# Triple_Phase_Bridge.net
KiCad netlist of a schematic drawn in Altium Designer
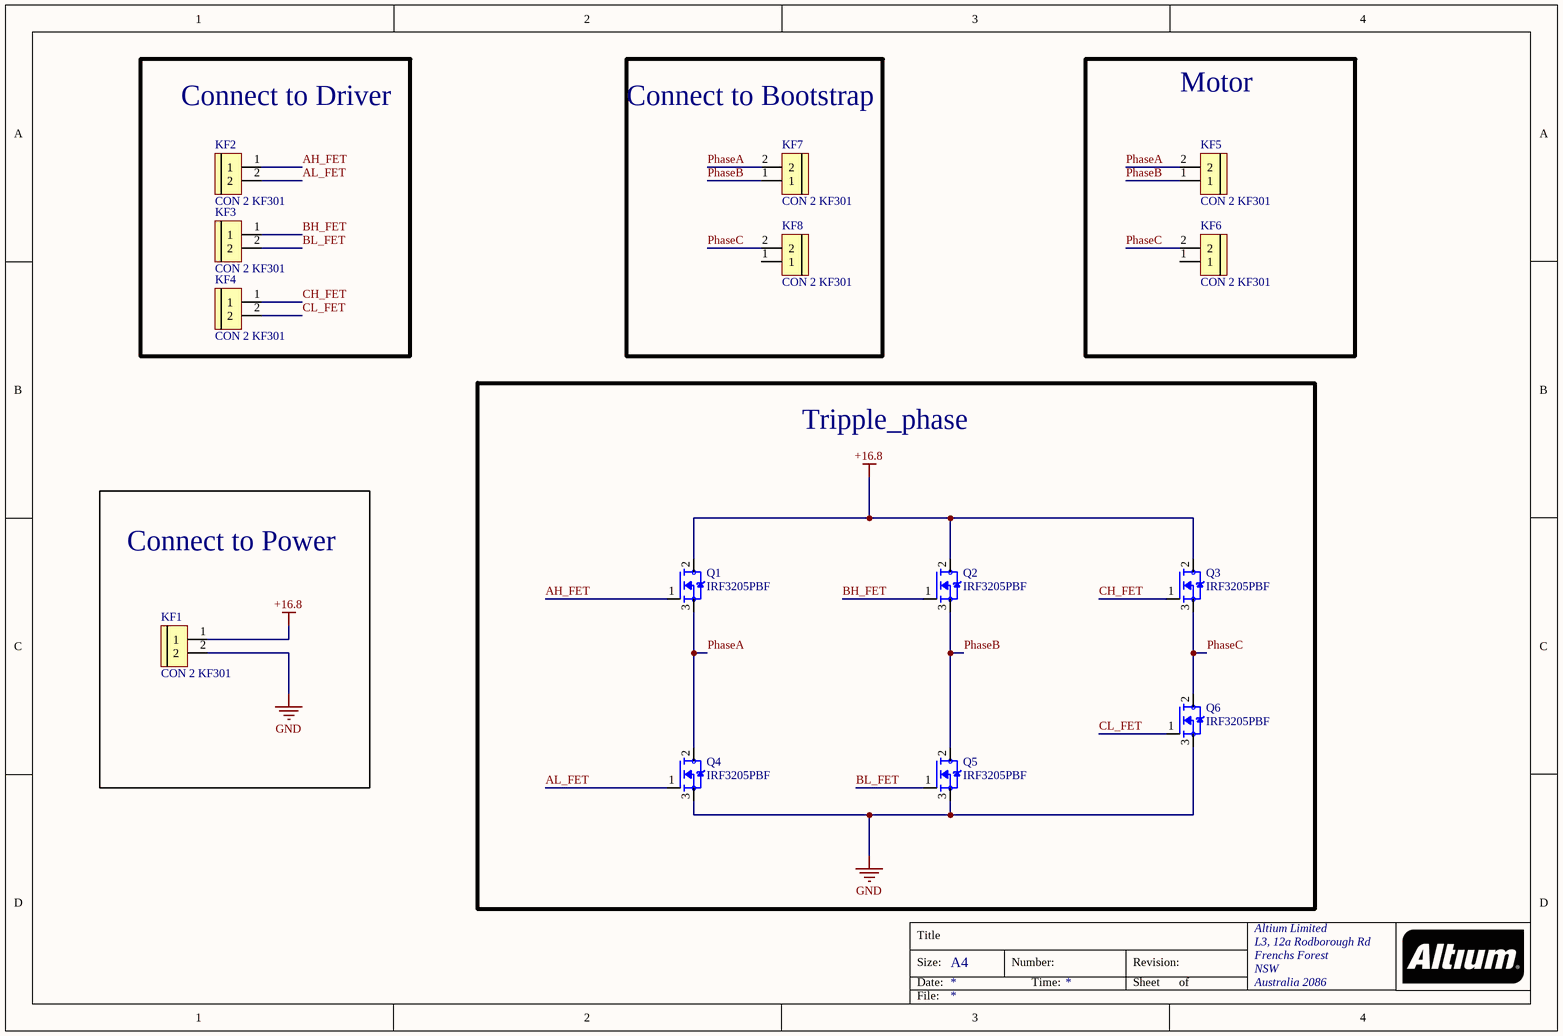
[diagram p0: Triple_Phase_Bridge.SchDoc]

(export (version "E")
  (design (tool "Eeschema 10.0.6"))
  (components
    (comp (ref "KF1")
      (value "CON 2 KF301")
      (footprint "Con 2 KF301 5.08")
      (description "Cắm")
      (libsource (lib "Connector") (part "CON 2 KF301"))
    )
    (comp (ref "KF2")
      (value "CON 2 KF301")
      (footprint "Con 2 KF301 5.08")
      (description "Cắm")
      (libsource (lib "Connector") (part "CON 2 KF301"))
    )
    (comp (ref "KF3")
      (value "CON 2 KF301")
      (footprint "Con 2 KF301 5.08")
      (description "Cắm")
      (libsource (lib "Connector") (part "CON 2 KF301"))
    )
    (comp (ref "KF4")
      (value "CON 2 KF301")
      (footprint "Con 2 KF301 5.08")
      (description "Cắm")
      (libsource (lib "Connector") (part "CON 2 KF301"))
    )
    (comp (ref "KF5")
      (value "CON 2 KF301")
      (footprint "Con 2 KF301 5.08")
      (description "Cắm")
      (libsource (lib "") (part "CON 2 KF301_1"))
    )
    (comp (ref "KF6")
      (value "CON 2 KF301")
      (footprint "Con 2 KF301 5.08")
      (description "Cắm")
      (libsource (lib "") (part "CON 2 KF301_1"))
    )
    (comp (ref "KF7")
      (value "CON 2 KF301")
      (footprint "Con 2 KF301 5.08")
      (description "Cắm")
      (libsource (lib "") (part "CON 2 KF301_1"))
    )
    (comp (ref "KF8")
      (value "CON 2 KF301")
      (footprint "Con 2 KF301 5.08")
      (description "Cắm")
      (libsource (lib "") (part "CON 2 KF301_1"))
    )
    (comp (ref "Q1")
      (value "IRF3205PBF")
      (footprint "TO254P1067X483X3124-3P")
      (description "N-Channel 55V 110A _Tc_ 200W _Tc_ Through Hole TO-220AB")
      (fields (field (name "MF") "Infineon Technologies"))
      (libsource (lib "IRF3205PBF") (part "IRF3205PBF"))
    )
    (comp (ref "Q2")
      (value "IRF3205PBF")
      (footprint "TO254P1067X483X3124-3P")
      (description "N-Channel 55V 110A _Tc_ 200W _Tc_ Through Hole TO-220AB")
      (fields (field (name "MF") "Infineon Technologies"))
      (libsource (lib "IRF3205PBF") (part "IRF3205PBF"))
    )
    (comp (ref "Q3")
      (value "IRF3205PBF")
      (footprint "TO254P1067X483X3124-3P")
      (description "N-Channel 55V 110A _Tc_ 200W _Tc_ Through Hole TO-220AB")
      (fields (field (name "MF") "Infineon Technologies"))
      (libsource (lib "IRF3205PBF") (part "IRF3205PBF"))
    )
    (comp (ref "Q4")
      (value "IRF3205PBF")
      (footprint "TO254P1067X483X3124-3P")
      (description "N-Channel 55V 110A _Tc_ 200W _Tc_ Through Hole TO-220AB")
      (fields (field (name "MF") "Infineon Technologies"))
      (libsource (lib "IRF3205PBF") (part "IRF3205PBF"))
    )
    (comp (ref "Q5")
      (value "IRF3205PBF")
      (footprint "TO254P1067X483X3124-3P")
      (description "N-Channel 55V 110A _Tc_ 200W _Tc_ Through Hole TO-220AB")
      (fields (field (name "MF") "Infineon Technologies"))
      (libsource (lib "IRF3205PBF") (part "IRF3205PBF"))
    )
    (comp (ref "Q6")
      (value "IRF3205PBF")
      (footprint "TO254P1067X483X3124-3P")
      (description "N-Channel 55V 110A _Tc_ 200W _Tc_ Through Hole TO-220AB")
      (fields (field (name "MF") "Infineon Technologies"))
      (libsource (lib "IRF3205PBF") (part "IRF3205PBF"))
    )
  )
  (nets
    (net (code "1") (name "+16.8") (class "Default")
      (node (ref "KF1") (pin "1") (pinfunction "1_1") (pintype "passive"))
      (node (ref "Q1") (pin "2") (pinfunction "D_2") (pintype "passive"))
      (node (ref "Q2") (pin "2") (pinfunction "D_2") (pintype "passive"))
      (node (ref "Q3") (pin "2") (pinfunction "D_2") (pintype "passive"))
    )
    (net (code "2") (name "/AH_FET") (class "Default")
      (node (ref "KF2") (pin "1") (pinfunction "1_1") (pintype "passive"))
      (node (ref "Q1") (pin "1") (pinfunction "G_1") (pintype "passive"))
    )
    (net (code "3") (name "/AL_FET") (class "Default")
      (node (ref "KF2") (pin "2") (pinfunction "2_2") (pintype "passive"))
      (node (ref "Q4") (pin "1") (pinfunction "G_1") (pintype "passive"))
    )
    (net (code "4") (name "/BH_FET") (class "Default")
      (node (ref "KF3") (pin "1") (pinfunction "1_1") (pintype "passive"))
      (node (ref "Q2") (pin "1") (pinfunction "G_1") (pintype "passive"))
    )
    (net (code "5") (name "/BL_FET") (class "Default")
      (node (ref "KF3") (pin "2") (pinfunction "2_2") (pintype "passive"))
      (node (ref "Q5") (pin "1") (pinfunction "G_1") (pintype "passive"))
    )
    (net (code "6") (name "/CH_FET") (class "Default")
      (node (ref "KF4") (pin "1") (pinfunction "1_1") (pintype "passive"))
      (node (ref "Q3") (pin "1") (pinfunction "G_1") (pintype "passive"))
    )
    (net (code "7") (name "/CL_FET") (class "Default")
      (node (ref "KF4") (pin "2") (pinfunction "2_2") (pintype "passive"))
      (node (ref "Q6") (pin "1") (pinfunction "G_1") (pintype "passive"))
    )
    (net (code "8") (name "/PhaseA") (class "Default")
      (node (ref "KF5") (pin "2") (pinfunction "2_2") (pintype "passive"))
      (node (ref "KF7") (pin "2") (pinfunction "2_2") (pintype "passive"))
      (node (ref "Q1") (pin "3") (pinfunction "S_3") (pintype "passive"))
      (node (ref "Q4") (pin "2") (pinfunction "D_2") (pintype "passive"))
    )
    (net (code "9") (name "/PhaseB") (class "Default")
      (node (ref "KF5") (pin "1") (pinfunction "1_1") (pintype "passive"))
      (node (ref "KF7") (pin "1") (pinfunction "1_1") (pintype "passive"))
      (node (ref "Q2") (pin "3") (pinfunction "S_3") (pintype "passive"))
      (node (ref "Q5") (pin "2") (pinfunction "D_2") (pintype "passive"))
    )
    (net (code "10") (name "/PhaseC") (class "Default")
      (node (ref "KF6") (pin "2") (pinfunction "2_2") (pintype "passive"))
      (node (ref "KF8") (pin "2") (pinfunction "2_2") (pintype "passive"))
      (node (ref "Q3") (pin "3") (pinfunction "S_3") (pintype "passive"))
      (node (ref "Q6") (pin "2") (pinfunction "D_2") (pintype "passive"))
    )
    (net (code "11") (name "GND") (class "Default")
      (node (ref "KF1") (pin "2") (pinfunction "2_2") (pintype "passive"))
      (node (ref "Q4") (pin "3") (pinfunction "S_3") (pintype "passive"))
      (node (ref "Q5") (pin "3") (pinfunction "S_3") (pintype "passive"))
      (node (ref "Q6") (pin "3") (pinfunction "S_3") (pintype "passive"))
    )
    (net (code "12") (name "unconnected-(KF6-Pad1)") (class "Default")
      (node (ref "KF6") (pin "1") (pinfunction "1_1") (pintype "passive"))
    )
    (net (code "13") (name "unconnected-(KF8-Pad1)") (class "Default")
      (node (ref "KF8") (pin "1") (pinfunction "1_1") (pintype "passive"))
    )
  )
)
